# 05_PWMdriver.net
KiCad netlist of a schematic drawn in Altium Designer
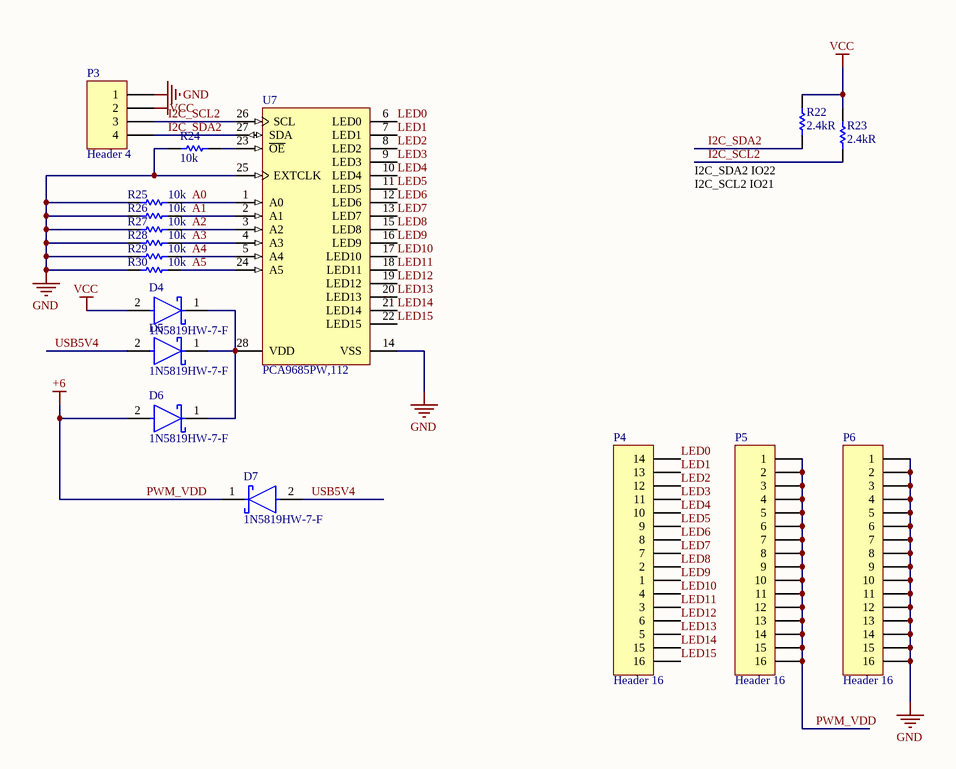
[diagram p0: 05_PWMdriver.SchDoc]

(export (version "E")
  (design (tool "Eeschema 10.0.6"))
  (components
    (comp (ref "D4")
      (value "1N5819HW-7-F")
      (footprint "FP-SOD123-MFG")
      (description "DIODE SCHOTTKY 40V 1A SOD123")
      (fields
        (field (name "OCTOPART") "https://octopart.com/1n5819hw-7-f-diodes+inc.-323197")
        (field (name "MANUFACTURER") "Diodes Inc")
      )
      (libsource (lib "Altium Content Vault") (part "1d6ec82d83fb6aee721767c19dac4b9"))
    )
    (comp (ref "D5")
      (value "1N5819HW-7-F")
      (footprint "FP-SOD123-MFG")
      (description "DIODE SCHOTTKY 40V 1A SOD123")
      (fields
        (field (name "OCTOPART") "https://octopart.com/1n5819hw-7-f-diodes+inc.-323197")
        (field (name "MANUFACTURER") "Diodes Inc")
      )
      (libsource (lib "Altium Content Vault") (part "1d6ec82d83fb6aee721767c19dac4b9"))
    )
    (comp (ref "D6")
      (value "1N5819HW-7-F")
      (footprint "FP-SOD123-MFG")
      (description "DIODE SCHOTTKY 40V 1A SOD123")
      (fields
        (field (name "OCTOPART") "https://octopart.com/1n5819hw-7-f-diodes+inc.-323197")
        (field (name "MANUFACTURER") "Diodes Inc")
      )
      (libsource (lib "Altium Content Vault") (part "1d6ec82d83fb6aee721767c19dac4b9"))
    )
    (comp (ref "D7")
      (value "1N5819HW-7-F")
      (footprint "FP-SOD123-MFG")
      (description "DIODE SCHOTTKY 40V 1A SOD123")
      (fields
        (field (name "OCTOPART") "https://octopart.com/1n5819hw-7-f-diodes+inc.-323197")
        (field (name "MANUFACTURER") "Diodes Inc")
      )
      (libsource (lib "Altium Content Vault") (part "1d6ec82d83fb6aee721767c19dac4b9"))
    )
    (comp (ref "P3")
      (value "Header 4")
      (footprint "HDR1X4")
      (description "Header, 4-Pin")
      (fields (field (name "PUBLISHER") "Altium Limited"))
      (libsource (lib "Miscellaneous Connectors") (part "Header 4"))
    )
    (comp (ref "P4")
      (value "Header 16")
      (footprint "HDR1X16")
      (description "Header, 16-Pin")
      (fields (field (name "PUBLISHER") "Altium Limited"))
      (libsource (lib "Miscellaneous Connectors") (part "Header 16"))
    )
    (comp (ref "P5")
      (value "Header 16")
      (footprint "HDR1X16")
      (description "Header, 16-Pin")
      (fields (field (name "PUBLISHER") "Altium Limited"))
      (libsource (lib "") (part "Header 16_1"))
    )
    (comp (ref "P6")
      (value "Header 16")
      (footprint "HDR1X16")
      (description "Header, 16-Pin")
      (fields (field (name "PUBLISHER") "Altium Limited"))
      (libsource (lib "") (part "Header 16_1"))
    )
    (comp (ref "R22")
      (value "2.4kR")
      (footprint "RESC1608X50X30ML20T20")
      (fields (field (name "PART NUMBER") "RR0816P-242-D") (field (name "MANUFACTURER") "Susumu"))
      (libsource (lib "Altium Content Vault") (part "RES"))
    )
    (comp (ref "R23")
      (value "2.4kR")
      (footprint "RESC1608X50X30ML20T20")
      (fields (field (name "PART NUMBER") "RR0816P-242-D") (field (name "MANUFACTURER") "Susumu"))
      (libsource (lib "Altium Content Vault") (part "RES"))
    )
    (comp (ref "R24")
      (value "10k")
      (footprint "RESC1609X55X30LL15T15")
      (description "Chip Resistor, 10 KOhm, +/- 1%, 0.1 W, -55 to 155 degC, 0603 (1608 Metric), RoHS, Tape and Reel")
      (fields (field (name "TOLERANCE") "1%") (field (name "MANUFACTURER") "Panasonic"))
      (libsource (lib "Altium Content Vault") (part "RES-2"))
    )
    (comp (ref "R25")
      (value "10k")
      (footprint "RESC1609X55X30LL15T15")
      (description "Chip Resistor, 10 KOhm, +/- 1%, 0.1 W, -55 to 155 degC, 0603 (1608 Metric), RoHS, Tape and Reel")
      (fields (field (name "TOLERANCE") "1%") (field (name "MANUFACTURER") "Panasonic"))
      (libsource (lib "Altium Content Vault") (part "RES-2"))
    )
    (comp (ref "R26")
      (value "10k")
      (footprint "RESC1609X55X30LL15T15")
      (description "Chip Resistor, 10 KOhm, +/- 1%, 0.1 W, -55 to 155 degC, 0603 (1608 Metric), RoHS, Tape and Reel")
      (fields (field (name "TOLERANCE") "1%") (field (name "MANUFACTURER") "Panasonic"))
      (libsource (lib "Altium Content Vault") (part "RES-2"))
    )
    (comp (ref "R27")
      (value "10k")
      (footprint "RESC1609X55X30LL15T15")
      (description "Chip Resistor, 10 KOhm, +/- 1%, 0.1 W, -55 to 155 degC, 0603 (1608 Metric), RoHS, Tape and Reel")
      (fields (field (name "TOLERANCE") "1%") (field (name "MANUFACTURER") "Panasonic"))
      (libsource (lib "Altium Content Vault") (part "RES-2"))
    )
    (comp (ref "R28")
      (value "10k")
      (footprint "RESC1609X55X30LL15T15")
      (description "Chip Resistor, 10 KOhm, +/- 1%, 0.1 W, -55 to 155 degC, 0603 (1608 Metric), RoHS, Tape and Reel")
      (fields (field (name "TOLERANCE") "1%") (field (name "MANUFACTURER") "Panasonic"))
      (libsource (lib "Altium Content Vault") (part "RES-2"))
    )
    (comp (ref "R29")
      (value "10k")
      (footprint "RESC1609X55X30LL15T15")
      (description "Chip Resistor, 10 KOhm, +/- 1%, 0.1 W, -55 to 155 degC, 0603 (1608 Metric), RoHS, Tape and Reel")
      (fields (field (name "TOLERANCE") "1%") (field (name "MANUFACTURER") "Panasonic"))
      (libsource (lib "Altium Content Vault") (part "RES-2"))
    )
    (comp (ref "R30")
      (value "10k")
      (footprint "RESC1609X55X30LL15T15")
      (description "Chip Resistor, 10 KOhm, +/- 1%, 0.1 W, -55 to 155 degC, 0603 (1608 Metric), RoHS, Tape and Reel")
      (fields (field (name "TOLERANCE") "1%") (field (name "MANUFACTURER") "Panasonic"))
      (libsource (lib "Altium Content Vault") (part "RES-2"))
    )
    (comp (ref "U7")
      (value "PCA9685PW,112")
      (footprint "SOT361-1_V")
      (fields (field (name "PARTNUMBER") "PCA9685"))
      (libsource (lib "Altium Content Vault") (part "NXP-PCA9685-SOT361-1"))
    )
  )
  (nets
    (net (code "1") (name "+6") (class "Default")
      (node (ref "D6") (pin "2") (pinfunction "A_2") (pintype "passive"))
      (node (ref "D7") (pin "1") (pinfunction "C_1") (pintype "passive"))
      (node (ref "P5") (pin "1") (pinfunction "1_1") (pintype "passive"))
      (node (ref "P5") (pin "10") (pinfunction "10_10") (pintype "passive"))
      (node (ref "P5") (pin "11") (pinfunction "11_11") (pintype "passive"))
      (node (ref "P5") (pin "12") (pinfunction "12_12") (pintype "passive"))
      (node (ref "P5") (pin "13") (pinfunction "13_13") (pintype "passive"))
      (node (ref "P5") (pin "14") (pinfunction "14_14") (pintype "passive"))
      (node (ref "P5") (pin "15") (pinfunction "15_15") (pintype "passive"))
      (node (ref "P5") (pin "16") (pinfunction "16_16") (pintype "passive"))
      (node (ref "P5") (pin "2") (pinfunction "2_2") (pintype "passive"))
      (node (ref "P5") (pin "3") (pinfunction "3_3") (pintype "passive"))
      (node (ref "P5") (pin "4") (pinfunction "4_4") (pintype "passive"))
      (node (ref "P5") (pin "5") (pinfunction "5_5") (pintype "passive"))
      (node (ref "P5") (pin "6") (pinfunction "6_6") (pintype "passive"))
      (node (ref "P5") (pin "7") (pinfunction "7_7") (pintype "passive"))
      (node (ref "P5") (pin "8") (pinfunction "8_8") (pintype "passive"))
      (node (ref "P5") (pin "9") (pinfunction "9_9") (pintype "passive"))
    )
    (net (code "2") (name "/A0") (class "Default")
      (node (ref "R25") (pin "1") (pinfunction "1_1") (pintype "passive"))
      (node (ref "U7") (pin "1") (pinfunction "A0_1") (pintype "input"))
    )
    (net (code "3") (name "/A1") (class "Default")
      (node (ref "R26") (pin "1") (pinfunction "1_1") (pintype "passive"))
      (node (ref "U7") (pin "2") (pinfunction "A1_2") (pintype "input"))
    )
    (net (code "4") (name "/A2") (class "Default")
      (node (ref "R27") (pin "1") (pinfunction "1_1") (pintype "passive"))
      (node (ref "U7") (pin "3") (pinfunction "A2_3") (pintype "input"))
    )
    (net (code "5") (name "/A3") (class "Default")
      (node (ref "R28") (pin "1") (pinfunction "1_1") (pintype "passive"))
      (node (ref "U7") (pin "4") (pinfunction "A3_4") (pintype "input"))
    )
    (net (code "6") (name "/A4") (class "Default")
      (node (ref "R29") (pin "1") (pinfunction "1_1") (pintype "passive"))
      (node (ref "U7") (pin "5") (pinfunction "A4_5") (pintype "input"))
    )
    (net (code "7") (name "/A5") (class "Default")
      (node (ref "R30") (pin "1") (pinfunction "1_1") (pintype "passive"))
      (node (ref "U7") (pin "24") (pinfunction "A5_24") (pintype "input"))
    )
    (net (code "8") (name "/I2C_SCL2") (class "Default")
      (node (ref "P3") (pin "3") (pinfunction "3_3") (pintype "passive"))
      (node (ref "R23") (pin "1") (pinfunction "1_1") (pintype "passive"))
      (node (ref "U7") (pin "26") (pinfunction "SCL_26") (pintype "input"))
    )
    (net (code "9") (name "/I2C_SDA2") (class "Default")
      (node (ref "P3") (pin "4") (pinfunction "4_4") (pintype "passive"))
      (node (ref "R22") (pin "1") (pinfunction "1_1") (pintype "passive"))
      (node (ref "U7") (pin "27") (pinfunction "SDA_27") (pintype "bidirectional"))
    )
    (net (code "10") (name "/LED0") (class "Default")
      (node (ref "P4") (pin "14") (pinfunction "14_14") (pintype "passive"))
      (node (ref "U7") (pin "6") (pinfunction "LED0_6") (pintype "tri_state"))
    )
    (net (code "11") (name "/LED1") (class "Default")
      (node (ref "P4") (pin "13") (pinfunction "13_13") (pintype "passive"))
      (node (ref "U7") (pin "7") (pinfunction "LED1_7") (pintype "tri_state"))
    )
    (net (code "12") (name "/LED2") (class "Default")
      (node (ref "P4") (pin "12") (pinfunction "12_12") (pintype "passive"))
      (node (ref "U7") (pin "8") (pinfunction "LED2_8") (pintype "tri_state"))
    )
    (net (code "13") (name "/LED3") (class "Default")
      (node (ref "P4") (pin "11") (pinfunction "11_11") (pintype "passive"))
      (node (ref "U7") (pin "9") (pinfunction "LED3_9") (pintype "tri_state"))
    )
    (net (code "14") (name "/LED4") (class "Default")
      (node (ref "P4") (pin "10") (pinfunction "10_10") (pintype "passive"))
      (node (ref "U7") (pin "10") (pinfunction "LED4_10") (pintype "tri_state"))
    )
    (net (code "15") (name "/LED5") (class "Default")
      (node (ref "P4") (pin "9") (pinfunction "9_9") (pintype "passive"))
      (node (ref "U7") (pin "11") (pinfunction "LED5_11") (pintype "tri_state"))
    )
    (net (code "16") (name "/LED6") (class "Default")
      (node (ref "P4") (pin "8") (pinfunction "8_8") (pintype "passive"))
      (node (ref "U7") (pin "12") (pinfunction "LED6_12") (pintype "tri_state"))
    )
    (net (code "17") (name "/LED7") (class "Default")
      (node (ref "P4") (pin "7") (pinfunction "7_7") (pintype "passive"))
      (node (ref "U7") (pin "13") (pinfunction "LED7_13") (pintype "tri_state"))
    )
    (net (code "18") (name "/LED8") (class "Default")
      (node (ref "P4") (pin "2") (pinfunction "2_2") (pintype "passive"))
      (node (ref "U7") (pin "15") (pinfunction "LED8_15") (pintype "tri_state"))
    )
    (net (code "19") (name "/LED9") (class "Default")
      (node (ref "P4") (pin "1") (pinfunction "1_1") (pintype "passive"))
      (node (ref "U7") (pin "16") (pinfunction "LED9_16") (pintype "tri_state"))
    )
    (net (code "20") (name "/LED10") (class "Default")
      (node (ref "P4") (pin "4") (pinfunction "4_4") (pintype "passive"))
      (node (ref "U7") (pin "17") (pinfunction "LED10_17") (pintype "tri_state"))
    )
    (net (code "21") (name "/LED11") (class "Default")
      (node (ref "P4") (pin "3") (pinfunction "3_3") (pintype "passive"))
      (node (ref "U7") (pin "18") (pinfunction "LED11_18") (pintype "tri_state"))
    )
    (net (code "22") (name "/LED12") (class "Default")
      (node (ref "P4") (pin "6") (pinfunction "6_6") (pintype "passive"))
      (node (ref "U7") (pin "19") (pinfunction "LED12_19") (pintype "tri_state"))
    )
    (net (code "23") (name "/LED13") (class "Default")
      (node (ref "P4") (pin "5") (pinfunction "5_5") (pintype "passive"))
      (node (ref "U7") (pin "20") (pinfunction "LED13_20") (pintype "tri_state"))
    )
    (net (code "24") (name "/LED14") (class "Default")
      (node (ref "P4") (pin "15") (pinfunction "15_15") (pintype "passive"))
      (node (ref "U7") (pin "21") (pinfunction "LED14_21") (pintype "tri_state"))
    )
    (net (code "25") (name "/LED15") (class "Default")
      (node (ref "P4") (pin "16") (pinfunction "16_16") (pintype "passive"))
      (node (ref "U7") (pin "22") (pinfunction "LED15_22") (pintype "tri_state"))
    )
    (net (code "26") (name "/USB5V4") (class "Default")
      (node (ref "D5") (pin "2") (pinfunction "A_2") (pintype "passive"))
      (node (ref "D7") (pin "2") (pinfunction "A_2") (pintype "passive"))
    )
    (net (code "27") (name "GND") (class "Default")
      (node (ref "P3") (pin "1") (pinfunction "1_1") (pintype "passive"))
      (node (ref "P6") (pin "1") (pinfunction "1_1") (pintype "passive"))
      (node (ref "P6") (pin "10") (pinfunction "10_10") (pintype "passive"))
      (node (ref "P6") (pin "11") (pinfunction "11_11") (pintype "passive"))
      (node (ref "P6") (pin "12") (pinfunction "12_12") (pintype "passive"))
      (node (ref "P6") (pin "13") (pinfunction "13_13") (pintype "passive"))
      (node (ref "P6") (pin "14") (pinfunction "14_14") (pintype "passive"))
      (node (ref "P6") (pin "15") (pinfunction "15_15") (pintype "passive"))
      (node (ref "P6") (pin "16") (pinfunction "16_16") (pintype "passive"))
      (node (ref "P6") (pin "2") (pinfunction "2_2") (pintype "passive"))
      (node (ref "P6") (pin "3") (pinfunction "3_3") (pintype "passive"))
      (node (ref "P6") (pin "4") (pinfunction "4_4") (pintype "passive"))
      (node (ref "P6") (pin "5") (pinfunction "5_5") (pintype "passive"))
      (node (ref "P6") (pin "6") (pinfunction "6_6") (pintype "passive"))
      (node (ref "P6") (pin "7") (pinfunction "7_7") (pintype "passive"))
      (node (ref "P6") (pin "8") (pinfunction "8_8") (pintype "passive"))
      (node (ref "P6") (pin "9") (pinfunction "9_9") (pintype "passive"))
      (node (ref "R24") (pin "2") (pinfunction "2_2") (pintype "passive"))
      (node (ref "R25") (pin "2") (pinfunction "2_2") (pintype "passive"))
      (node (ref "R26") (pin "2") (pinfunction "2_2") (pintype "passive"))
      (node (ref "R27") (pin "2") (pinfunction "2_2") (pintype "passive"))
      (node (ref "R28") (pin "2") (pinfunction "2_2") (pintype "passive"))
      (node (ref "R29") (pin "2") (pinfunction "2_2") (pintype "passive"))
      (node (ref "R30") (pin "2") (pinfunction "2_2") (pintype "passive"))
      (node (ref "U7") (pin "14") (pinfunction "VSS_14") (pintype "power_in"))
      (node (ref "U7") (pin "25") (pinfunction "EXTCLK_25") (pintype "input"))
    )
    (net (code "28") (name "Net-(D4-C)") (class "Default")
      (node (ref "D4") (pin "1") (pinfunction "C_1") (pintype "passive"))
      (node (ref "D5") (pin "1") (pinfunction "C_1") (pintype "passive"))
      (node (ref "D6") (pin "1") (pinfunction "C_1") (pintype "passive"))
      (node (ref "U7") (pin "28") (pinfunction "VDD_28") (pintype "power_in"))
    )
    (net (code "29") (name "Net-(U7-~{OE})") (class "Default")
      (node (ref "R24") (pin "1") (pinfunction "1_1") (pintype "passive"))
      (node (ref "U7") (pin "23") (pinfunction "~{OE}_23") (pintype "input"))
    )
    (net (code "30") (name "VCC") (class "Default")
      (node (ref "D4") (pin "2") (pinfunction "A_2") (pintype "passive"))
      (node (ref "P3") (pin "2") (pinfunction "2_2") (pintype "passive"))
      (node (ref "R22") (pin "2") (pinfunction "2_2") (pintype "passive"))
      (node (ref "R23") (pin "2") (pinfunction "2_2") (pintype "passive"))
    )
  )
)
